# MPU9250.net
KiCad netlist of a schematic drawn in Altium Designer
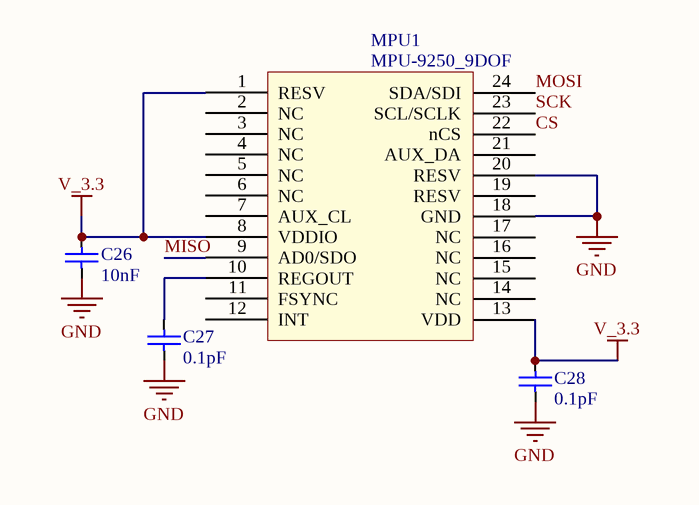
[diagram p0: MPU9250.SchDoc]

(export (version "E")
  (design (tool "Eeschema 10.0.6"))
  (components
    (comp (ref "C26")
      (value "10nF")
      (footprint "CAP0603R")
      (description "Capacitor")
      (fields
        (field (name "MANUFACTURER") "Microchip Technology")
        (field (name "MANUFACTURER PART NUM") "MIC5378YC5-TR")
      )
      (libsource (lib "SuperBot_Schlib1") (part "C"))
    )
    (comp (ref "C27")
      (value "0.1pF")
      (footprint "CAP0603R")
      (description "Capacitor")
      (fields
        (field (name "MANUFACTURER") "Microchip Technology")
        (field (name "MANUFACTURER PART NUM") "MIC5378YC5-TR")
      )
      (libsource (lib "SuperBot_Schlib1") (part "C"))
    )
    (comp (ref "C28")
      (value "0.1pF")
      (footprint "CAP0603R")
      (description "Capacitor")
      (fields
        (field (name "MANUFACTURER") "Microchip Technology")
        (field (name "MANUFACTURER PART NUM") "MIC5378YC5-TR")
      )
      (libsource (lib "SuperBot_Schlib1") (part "C"))
    )
    (comp (ref "MPU1")
      (value "MPU-9250_9DOF")
      (footprint "QFN424_MPU-9250")
      (description "IMU ACCEL/GYRO/MAG I2C/SPI 24QFN")
      (libsource (lib "SuperBot_Schlib1") (part "MPU-9250"))
    )
  )
  (nets
    (net (code "1") (name "/CS") (class "Default")
      (node (ref "MPU1") (pin "22") (pinfunction "nCS_22") (pintype "passive"))
    )
    (net (code "2") (name "/MISO") (class "Default")
      (node (ref "MPU1") (pin "9") (pinfunction "AD0/SDO_9") (pintype "passive"))
    )
    (net (code "3") (name "/MOSI") (class "Default")
      (node (ref "MPU1") (pin "24") (pinfunction "SDA/SDI_24") (pintype "passive"))
    )
    (net (code "4") (name "/SCK") (class "Default")
      (node (ref "MPU1") (pin "23") (pinfunction "SCL/SCLK_23") (pintype "passive"))
    )
    (net (code "5") (name "GND") (class "Default")
      (node (ref "C26") (pin "2") (pinfunction "2_2") (pintype "passive"))
      (node (ref "C27") (pin "2") (pinfunction "2_2") (pintype "passive"))
      (node (ref "C28") (pin "2") (pinfunction "2_2") (pintype "passive"))
      (node (ref "MPU1") (pin "18") (pinfunction "GND_18") (pintype "passive"))
      (node (ref "MPU1") (pin "20") (pinfunction "RESV_20") (pintype "passive"))
    )
    (net (code "6") (name "Net-(MPU1-REGOUT)") (class "Default")
      (node (ref "C27") (pin "1") (pinfunction "1_1") (pintype "passive"))
      (node (ref "MPU1") (pin "10") (pinfunction "REGOUT_10") (pintype "passive"))
    )
    (net (code "7") (name "V_3.3") (class "Default")
      (node (ref "C26") (pin "1") (pinfunction "1_1") (pintype "passive"))
      (node (ref "C28") (pin "1") (pinfunction "1_1") (pintype "passive"))
      (node (ref "MPU1") (pin "1") (pinfunction "RESV_1") (pintype "passive"))
      (node (ref "MPU1") (pin "13") (pinfunction "VDD_13") (pintype "passive"))
      (node (ref "MPU1") (pin "8") (pinfunction "VDDIO_8") (pintype "passive"))
    )
    (net (code "8") (name "unconnected-(MPU1-AUX_CL-Pad7)") (class "Default")
      (node (ref "MPU1") (pin "7") (pinfunction "AUX_CL_7") (pintype "passive"))
    )
    (net (code "9") (name "unconnected-(MPU1-AUX_DA-Pad21)") (class "Default")
      (node (ref "MPU1") (pin "21") (pinfunction "AUX_DA_21") (pintype "passive"))
    )
    (net (code "10") (name "unconnected-(MPU1-FSYNC-Pad11)") (class "Default")
      (node (ref "MPU1") (pin "11") (pinfunction "FSYNC_11") (pintype "passive"))
    )
    (net (code "11") (name "unconnected-(MPU1-INT-Pad12)") (class "Default")
      (node (ref "MPU1") (pin "12") (pinfunction "INT_12") (pintype "passive"))
    )
    (net (code "12") (name "unconnected-(MPU1-NC-Pad2)") (class "Default")
      (node (ref "MPU1") (pin "2") (pinfunction "NC_2") (pintype "passive"))
    )
    (net (code "13") (name "unconnected-(MPU1-NC-Pad3)") (class "Default")
      (node (ref "MPU1") (pin "3") (pinfunction "NC_3") (pintype "passive"))
    )
    (net (code "14") (name "unconnected-(MPU1-NC-Pad4)") (class "Default")
      (node (ref "MPU1") (pin "4") (pinfunction "NC_4") (pintype "passive"))
    )
    (net (code "15") (name "unconnected-(MPU1-NC-Pad5)") (class "Default")
      (node (ref "MPU1") (pin "5") (pinfunction "NC_5") (pintype "passive"))
    )
    (net (code "16") (name "unconnected-(MPU1-NC-Pad6)") (class "Default")
      (node (ref "MPU1") (pin "6") (pinfunction "NC_6") (pintype "passive"))
    )
    (net (code "17") (name "unconnected-(MPU1-NC-Pad14)") (class "Default")
      (node (ref "MPU1") (pin "14") (pinfunction "NC_14") (pintype "passive"))
    )
    (net (code "18") (name "unconnected-(MPU1-NC-Pad15)") (class "Default")
      (node (ref "MPU1") (pin "15") (pinfunction "NC_15") (pintype "passive"))
    )
    (net (code "19") (name "unconnected-(MPU1-NC-Pad16)") (class "Default")
      (node (ref "MPU1") (pin "16") (pinfunction "NC_16") (pintype "passive"))
    )
    (net (code "20") (name "unconnected-(MPU1-NC-Pad17)") (class "Default")
      (node (ref "MPU1") (pin "17") (pinfunction "NC_17") (pintype "passive"))
    )
    (net (code "21") (name "unconnected-(MPU1-RESV-Pad19)") (class "Default")
      (node (ref "MPU1") (pin "19") (pinfunction "RESV_19") (pintype "passive"))
    )
  )
)
